# VALVEBOARD_ValveDrive.net
KiCad netlist of a schematic drawn in Altium Designer
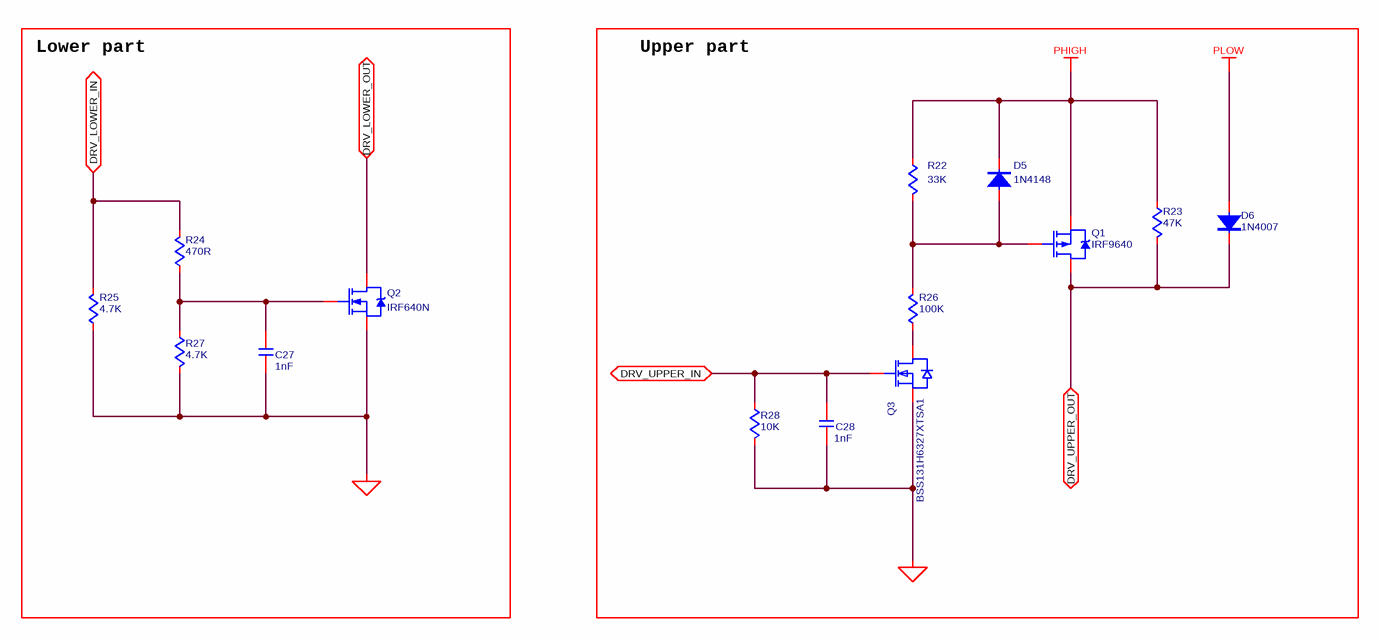
[diagram p0: VALVEBOARD_ValveDrive.SchDoc]

(export (version "E")
  (design (tool "Eeschema 10.0.6"))
  (components
    (comp (ref "C27")
      (value "1nF")
      (footprint "zynq:C0603")
      (fields (field (name "VOLTAGE") "25V") (field (name "Comment") "C-NOMO"))
      (libsource (lib "zynq") (part "C-NOMO"))
    )
    (comp (ref "C28")
      (value "1nF")
      (footprint "zynq:C0603")
      (fields (field (name "VOLTAGE") "25V") (field (name "Comment") "C-NOMO"))
      (libsource (lib "zynq") (part "C-NOMO"))
    )
    (comp (ref "D5") (value "1N4148") (footprint "sod-123") (libsource (lib "") (part "DIOD1_1")))
    (comp (ref "D6") (value "1N4007") (footprint "zynq:1N4148") (libsource (lib "zynq") (part "DIOD1")))
    (comp (ref "Q1")
      (value "IRF9640")
      (footprint "TO-220AB")
      (description "P-Channel Power MOSFET")
      (fields (field (name "PUBLISHER") "Altium Limited"))
      (libsource (lib "zynq") (part "IRF9640"))
    )
    (comp (ref "Q2")
      (value "IRF640N")
      (footprint "zynq:TO-220AB")
      (description "N-Channel Power MOSFET")
      (fields (field (name "PUBLISHER") "Altium Limited"))
      (libsource (lib "zynq") (part "IRF640N"))
    )
    (comp (ref "Q3")
      (value "BSS131H6327XTSA1")
      (footprint "BSS131H6327XTSA1")
      (libsource (lib "zynq") (part "BSS131H6327XTSA1"))
    )
    (comp (ref "R22")
      (value "33K")
      (footprint "zynq:R0805")
      (fields (field (name "Comment") "R"))
      (libsource (lib "zynq") (part "R"))
    )
    (comp (ref "R23")
      (value "47K")
      (footprint "R2512")
      (fields (field (name "Comment") "R"))
      (libsource (lib "zynq") (part "R"))
    )
    (comp (ref "R24")
      (value "470R")
      (footprint "zynq:R0603")
      (fields (field (name "Comment") "R"))
      (libsource (lib "zynq") (part "R"))
    )
    (comp (ref "R25")
      (value "4.7K")
      (footprint "zynq:R0603")
      (fields (field (name "Comment") "R"))
      (libsource (lib "zynq") (part "R"))
    )
    (comp (ref "R26")
      (value "100K")
      (footprint "zynq:R0805")
      (fields (field (name "Comment") "R"))
      (libsource (lib "zynq") (part "R"))
    )
    (comp (ref "R27")
      (value "4.7K")
      (footprint "zynq:R0603")
      (fields (field (name "Comment") "R"))
      (libsource (lib "zynq") (part "R"))
    )
    (comp (ref "R28")
      (value "10K")
      (footprint "zynq:R0603")
      (fields (field (name "Comment") "R"))
      (libsource (lib "zynq") (part "R"))
    )
  )
  (nets
    (net (code "1") (name "/DRV_LOWER_IN") (class "Default")
      (node (ref "R24") (pin "1") (pinfunction "1_1") (pintype "passive"))
      (node (ref "R25") (pin "1") (pinfunction "1_1") (pintype "passive"))
    )
    (net (code "2") (name "/DRV_LOWER_OUT") (class "Default")
      (node (ref "Q2") (pin "2") (pinfunction "D_2") (pintype "passive"))
    )
    (net (code "3") (name "/DRV_UPPER_IN") (class "Default")
      (node (ref "C28") (pin "2") (pinfunction "2_2") (pintype "passive"))
      (node (ref "Q3") (pin "G") (pinfunction "G_G") (pintype "passive"))
      (node (ref "R28") (pin "2") (pinfunction "2_2") (pintype "passive"))
    )
    (net (code "4") (name "/DRV_UPPER_OUT") (class "Default")
      (node (ref "D6") (pin "1") (pinfunction "1_1") (pintype "passive"))
      (node (ref "Q1") (pin "2") (pinfunction "D_2") (pintype "passive"))
      (node (ref "R23") (pin "1") (pinfunction "1_1") (pintype "passive"))
    )
    (net (code "5") (name "Net-(Q1-G)") (class "Default")
      (node (ref "D5") (pin "2") (pinfunction "2_2") (pintype "passive"))
      (node (ref "Q1") (pin "1") (pinfunction "G_1") (pintype "passive"))
      (node (ref "R22") (pin "1") (pinfunction "1_1") (pintype "passive"))
      (node (ref "R26") (pin "1") (pinfunction "1_1") (pintype "passive"))
    )
    (net (code "6") (name "Net-(Q2-G)") (class "Default")
      (node (ref "C27") (pin "2") (pinfunction "2_2") (pintype "passive"))
      (node (ref "Q2") (pin "1") (pinfunction "G_1") (pintype "passive"))
      (node (ref "R24") (pin "2") (pinfunction "2_2") (pintype "passive"))
      (node (ref "R27") (pin "2") (pinfunction "2_2") (pintype "passive"))
    )
    (net (code "7") (name "Net-(Q3-PadD)") (class "Default")
      (node (ref "Q3") (pin "D") (pinfunction "D_D") (pintype "passive"))
      (node (ref "R26") (pin "2") (pinfunction "2_2") (pintype "passive"))
    )
    (net (code "8") (name "PGND") (class "Default")
      (node (ref "C27") (pin "1") (pinfunction "1_1") (pintype "passive"))
      (node (ref "C28") (pin "1") (pinfunction "1_1") (pintype "passive"))
      (node (ref "Q2") (pin "3") (pinfunction "S_3") (pintype "passive"))
      (node (ref "Q3") (pin "S") (pinfunction "S_S") (pintype "passive"))
      (node (ref "R25") (pin "2") (pinfunction "2_2") (pintype "passive"))
      (node (ref "R27") (pin "1") (pinfunction "1_1") (pintype "passive"))
      (node (ref "R28") (pin "1") (pinfunction "1_1") (pintype "passive"))
    )
    (net (code "9") (name "PHIGH") (class "Default")
      (node (ref "D5") (pin "1") (pinfunction "1_1") (pintype "passive"))
      (node (ref "Q1") (pin "3") (pinfunction "S_3") (pintype "passive"))
      (node (ref "R22") (pin "2") (pinfunction "2_2") (pintype "passive"))
      (node (ref "R23") (pin "2") (pinfunction "2_2") (pintype "passive"))
    )
    (net (code "10") (name "PLOW") (class "Default")
      (node (ref "D6") (pin "2") (pinfunction "2_2") (pintype "passive"))
    )
  )
)
